# LPCB278_-_1_WIRE.net
KiCad netlist of a schematic drawn in Altium Designer
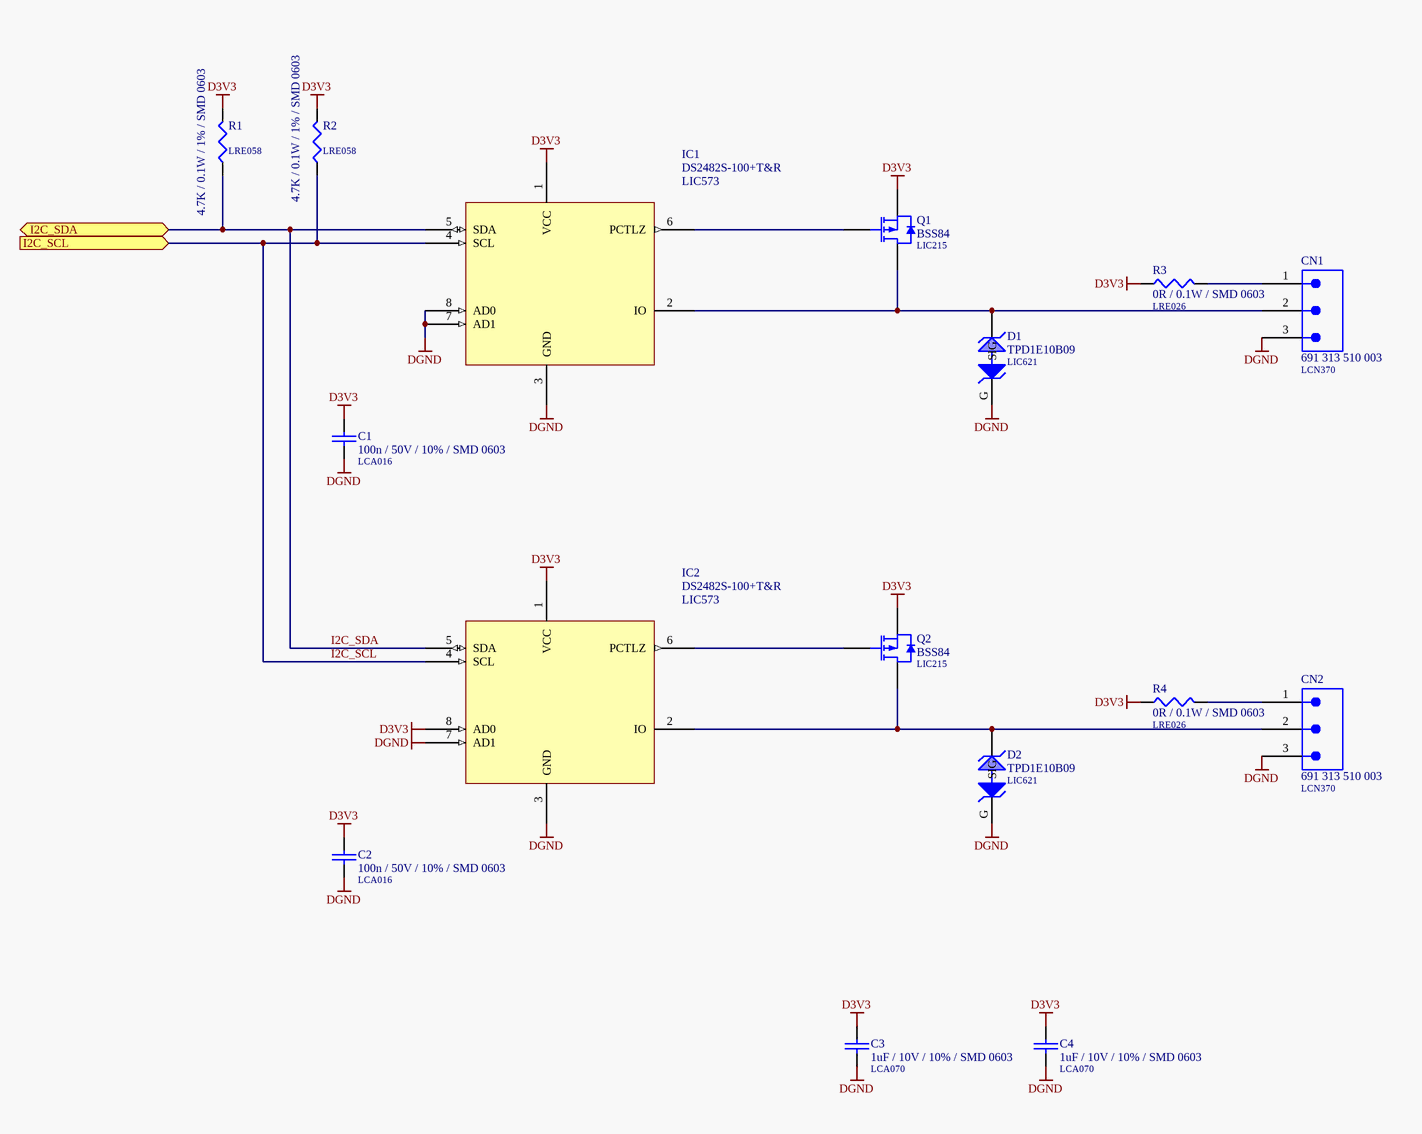
[diagram p0: LPCB278 - 1 WIRE.SchDoc]

(export (version "E")
  (design (tool "Eeschema 10.0.6"))
  (components
    (comp (ref "C1")
      (value "100n / 50V / 10% / SMD 0603")
      (footprint "LFP011__CC1608-0603-IPC7351_B")
      (description "Capacitor, Ceramic Chip, 100nF (0.1uF), 50V, 5%, SMD 0603 [LCA016]")
      (fields (field (name "LDL_NUMBER") "LCA016"))
      (libsource (lib "LDL_Capacitors") (part "100n / 50V / 10% / SMD 0603"))
    )
    (comp (ref "C2")
      (value "100n / 50V / 10% / SMD 0603")
      (footprint "LFP011__CC1608-0603-IPC7351_B")
      (description "Capacitor, Ceramic Chip, 100nF (0.1uF), 50V, 5%, SMD 0603 [LCA016]")
      (fields (field (name "LDL_NUMBER") "LCA016"))
      (libsource (lib "LDL_Capacitors") (part "100n / 50V / 10% / SMD 0603"))
    )
    (comp (ref "C3")
      (value "1uF / 10V / 10% / SMD 0603")
      (footprint "LFP011__CC1608-0603-IPC7351_B")
      (description "Capacitor, Ceramic Chip, 1uF, 10V, SMD 0603 [LCA070]")
      (fields (field (name "LDL_NUMBER") "LCA070"))
      (libsource (lib "LDL_Capacitors") (part "1uF / 10V / 10% / SMD 0603"))
    )
    (comp (ref "C4")
      (value "1uF / 10V / 10% / SMD 0603")
      (footprint "LFP011__CC1608-0603-IPC7351_B")
      (description "Capacitor, Ceramic Chip, 1uF, 10V, SMD 0603 [LCA070]")
      (fields (field (name "LDL_NUMBER") "LCA070"))
      (libsource (lib "LDL_Capacitors") (part "1uF / 10V / 10% / SMD 0603"))
    )
    (comp (ref "CN1")
      (value "691 313 510 003")
      (footprint "691 313 510 003")
      (description "Connector, Pluggable Terminal Block, 5.08mm, 3 Way, PTH")
      (fields (field (name "LDL_NUMBER") "LCN370"))
      (libsource (lib "LDL_Connectors") (part "691 313 510 003"))
    )
    (comp (ref "CN2")
      (value "691 313 510 003")
      (footprint "691 313 510 003")
      (description "Connector, Pluggable Terminal Block, 5.08mm, 3 Way, PTH")
      (fields (field (name "LDL_NUMBER") "LCN370"))
      (libsource (lib "LDL_Connectors") (part "691 313 510 003"))
    )
    (comp (ref "D1")
      (value "TPD1E10B09")
      (footprint "LFP157__R-PX1SON-N2")
      (description "Diode, ESD Protecion, 10pF, 9V Breakdown, SMD 0402 [LIC621]")
      (fields (field (name "LDL_NUMBER") "LIC621"))
      (libsource (lib "LDL_Semiconductors") (part "TPD1E10B09"))
    )
    (comp (ref "D2")
      (value "TPD1E10B09")
      (footprint "LFP157__R-PX1SON-N2")
      (description "Diode, ESD Protecion, 10pF, 9V Breakdown, SMD 0402 [LIC621]")
      (fields (field (name "LDL_NUMBER") "LIC621"))
      (libsource (lib "LDL_Semiconductors") (part "TPD1E10B09"))
    )
    (comp (ref "IC1")
      (value "DS2482S-100+T&R")
      (footprint "LFP069__R-8G")
      (description "IC, I2C to 1 Wire Bridge, SMD SOIC8")
      (fields (field (name "LDL_NUMBER") "LIC573"))
      (libsource (lib "LDL_Semiconductors") (part "DS2482S-100+T&R"))
    )
    (comp (ref "IC2")
      (value "DS2482S-100+T&R")
      (footprint "LFP069__R-8G")
      (description "IC, I2C to 1 Wire Bridge, SMD SOIC8")
      (fields (field (name "LDL_NUMBER") "LIC573"))
      (libsource (lib "LDL_Semiconductors") (part "DS2482S-100+T&R"))
    )
    (comp (ref "Q1")
      (value "BSS84")
      (footprint "LFP021__SOT23")
      (description "FET, P Channel, Logic Level, SMD SOT23 [LIC215]")
      (fields (field (name "LDL_NUMBER") "LIC215"))
      (libsource (lib "LDL_Semiconductors") (part "BSS84"))
    )
    (comp (ref "Q2")
      (value "BSS84")
      (footprint "LFP021__SOT23")
      (description "FET, P Channel, Logic Level, SMD SOT23 [LIC215]")
      (fields (field (name "LDL_NUMBER") "LIC215"))
      (libsource (lib "LDL_Semiconductors") (part "BSS84"))
    )
    (comp (ref "R1")
      (value "4.7K / 0.1W / 1% / SMD 0603")
      (footprint "LFP020__CR1608-0603-IPC7351_B")
      (description "Resistor, Ceramic Chip, 4K7, 0.1W, 1%, SMD 0603 [LRE058]")
      (fields (field (name "LDL_NUMBER") "LRE058"))
      (libsource (lib "LDL_Resistors") (part "4.7K / 0.1W / 1% / SMD 0603"))
    )
    (comp (ref "R2")
      (value "4.7K / 0.1W / 1% / SMD 0603")
      (footprint "LFP020__CR1608-0603-IPC7351_B")
      (description "Resistor, Ceramic Chip, 4K7, 0.1W, 1%, SMD 0603 [LRE058]")
      (fields (field (name "LDL_NUMBER") "LRE058"))
      (libsource (lib "LDL_Resistors") (part "4.7K / 0.1W / 1% / SMD 0603"))
    )
    (comp (ref "R3")
      (value "0R / 0.1W / SMD 0603")
      (footprint "LFP020__CR1608-0603-IPC7351_B")
      (description "Resistor, Ceramic Chip, 0R, 0.1W, SMD 0603 [LRE026]")
      (fields (field (name "LDL_NUMBER") "LRE026"))
      (libsource (lib "LDL_Resistors") (part "0R / 0.1W / SMD 0603"))
    )
    (comp (ref "R4")
      (value "0R / 0.1W / SMD 0603")
      (footprint "LFP020__CR1608-0603-IPC7351_B")
      (description "Resistor, Ceramic Chip, 0R, 0.1W, SMD 0603 [LRE026]")
      (fields (field (name "LDL_NUMBER") "LRE026"))
      (libsource (lib "LDL_Resistors") (part "0R / 0.1W / SMD 0603"))
    )
  )
  (nets
    (net (code "1") (name "/I2C_SCL") (class "Default")
      (node (ref "IC1") (pin "4") (pinfunction "SCL_4") (pintype "input"))
      (node (ref "IC2") (pin "4") (pinfunction "SCL_4") (pintype "input"))
      (node (ref "R2") (pin "1") (pintype "passive"))
    )
    (net (code "2") (name "/I2C_SDA") (class "Default")
      (node (ref "IC1") (pin "5") (pinfunction "SDA_5") (pintype "bidirectional"))
      (node (ref "IC2") (pin "5") (pinfunction "SDA_5") (pintype "bidirectional"))
      (node (ref "R1") (pin "1") (pintype "passive"))
    )
    (net (code "3") (name "D3V3") (class "Default")
      (node (ref "C1") (pin "1") (pintype "passive"))
      (node (ref "C2") (pin "1") (pintype "passive"))
      (node (ref "C3") (pin "1") (pintype "passive"))
      (node (ref "C4") (pin "1") (pintype "passive"))
      (node (ref "IC1") (pin "1") (pinfunction "VCC_1") (pintype "power_in"))
      (node (ref "IC2") (pin "1") (pinfunction "VCC_1") (pintype "power_in"))
      (node (ref "IC2") (pin "8") (pinfunction "AD0_8") (pintype "input"))
      (node (ref "Q1") (pin "2") (pinfunction "S_2") (pintype "passive"))
      (node (ref "Q2") (pin "2") (pinfunction "S_2") (pintype "passive"))
      (node (ref "R1") (pin "2") (pintype "passive"))
      (node (ref "R2") (pin "2") (pintype "passive"))
      (node (ref "R3") (pin "1") (pintype "passive"))
      (node (ref "R4") (pin "1") (pintype "passive"))
    )
    (net (code "4") (name "DGND") (class "Default")
      (node (ref "C1") (pin "2") (pintype "passive"))
      (node (ref "C2") (pin "2") (pintype "passive"))
      (node (ref "C3") (pin "2") (pintype "passive"))
      (node (ref "C4") (pin "2") (pintype "passive"))
      (node (ref "CN1") (pin "3") (pinfunction "3_3") (pintype "passive"))
      (node (ref "CN2") (pin "3") (pinfunction "3_3") (pintype "passive"))
      (node (ref "D1") (pin "G") (pinfunction "G_G") (pintype "passive"))
      (node (ref "D2") (pin "G") (pinfunction "G_G") (pintype "passive"))
      (node (ref "IC1") (pin "3") (pinfunction "GND_3") (pintype "power_in"))
      (node (ref "IC1") (pin "7") (pinfunction "AD1_7") (pintype "input"))
      (node (ref "IC1") (pin "8") (pinfunction "AD0_8") (pintype "input"))
      (node (ref "IC2") (pin "3") (pinfunction "GND_3") (pintype "power_in"))
      (node (ref "IC2") (pin "7") (pinfunction "AD1_7") (pintype "input"))
    )
    (net (code "5") (name "Net-(CN1-Pad1)") (class "Default")
      (node (ref "CN1") (pin "1") (pinfunction "1_1") (pintype "passive"))
      (node (ref "R3") (pin "2") (pintype "passive"))
    )
    (net (code "6") (name "Net-(CN2-Pad1)") (class "Default")
      (node (ref "CN2") (pin "1") (pinfunction "1_1") (pintype "passive"))
      (node (ref "R4") (pin "2") (pintype "passive"))
    )
    (net (code "7") (name "Net-(D1-SIG)") (class "Default")
      (node (ref "CN1") (pin "2") (pinfunction "2_2") (pintype "passive"))
      (node (ref "D1") (pin "2") (pinfunction "SIG_2") (pintype "passive"))
      (node (ref "IC1") (pin "2") (pinfunction "IO_2") (pintype "passive"))
      (node (ref "Q1") (pin "3") (pinfunction "D_3") (pintype "passive"))
    )
    (net (code "8") (name "Net-(D2-SIG)") (class "Default")
      (node (ref "CN2") (pin "2") (pinfunction "2_2") (pintype "passive"))
      (node (ref "D2") (pin "2") (pinfunction "SIG_2") (pintype "passive"))
      (node (ref "IC2") (pin "2") (pinfunction "IO_2") (pintype "passive"))
      (node (ref "Q2") (pin "3") (pinfunction "D_3") (pintype "passive"))
    )
    (net (code "9") (name "Net-(IC1-PCTLZ)") (class "Default")
      (node (ref "IC1") (pin "6") (pinfunction "PCTLZ_6") (pintype "output"))
      (node (ref "Q1") (pin "1") (pinfunction "G_1") (pintype "passive"))
    )
    (net (code "10") (name "Net-(IC2-PCTLZ)") (class "Default")
      (node (ref "IC2") (pin "6") (pinfunction "PCTLZ_6") (pintype "output"))
      (node (ref "Q2") (pin "1") (pinfunction "G_1") (pintype "passive"))
    )
  )
)
